# BuzzerBaseShieldv00.net
KiCad netlist of a schematic drawn in EAGLE
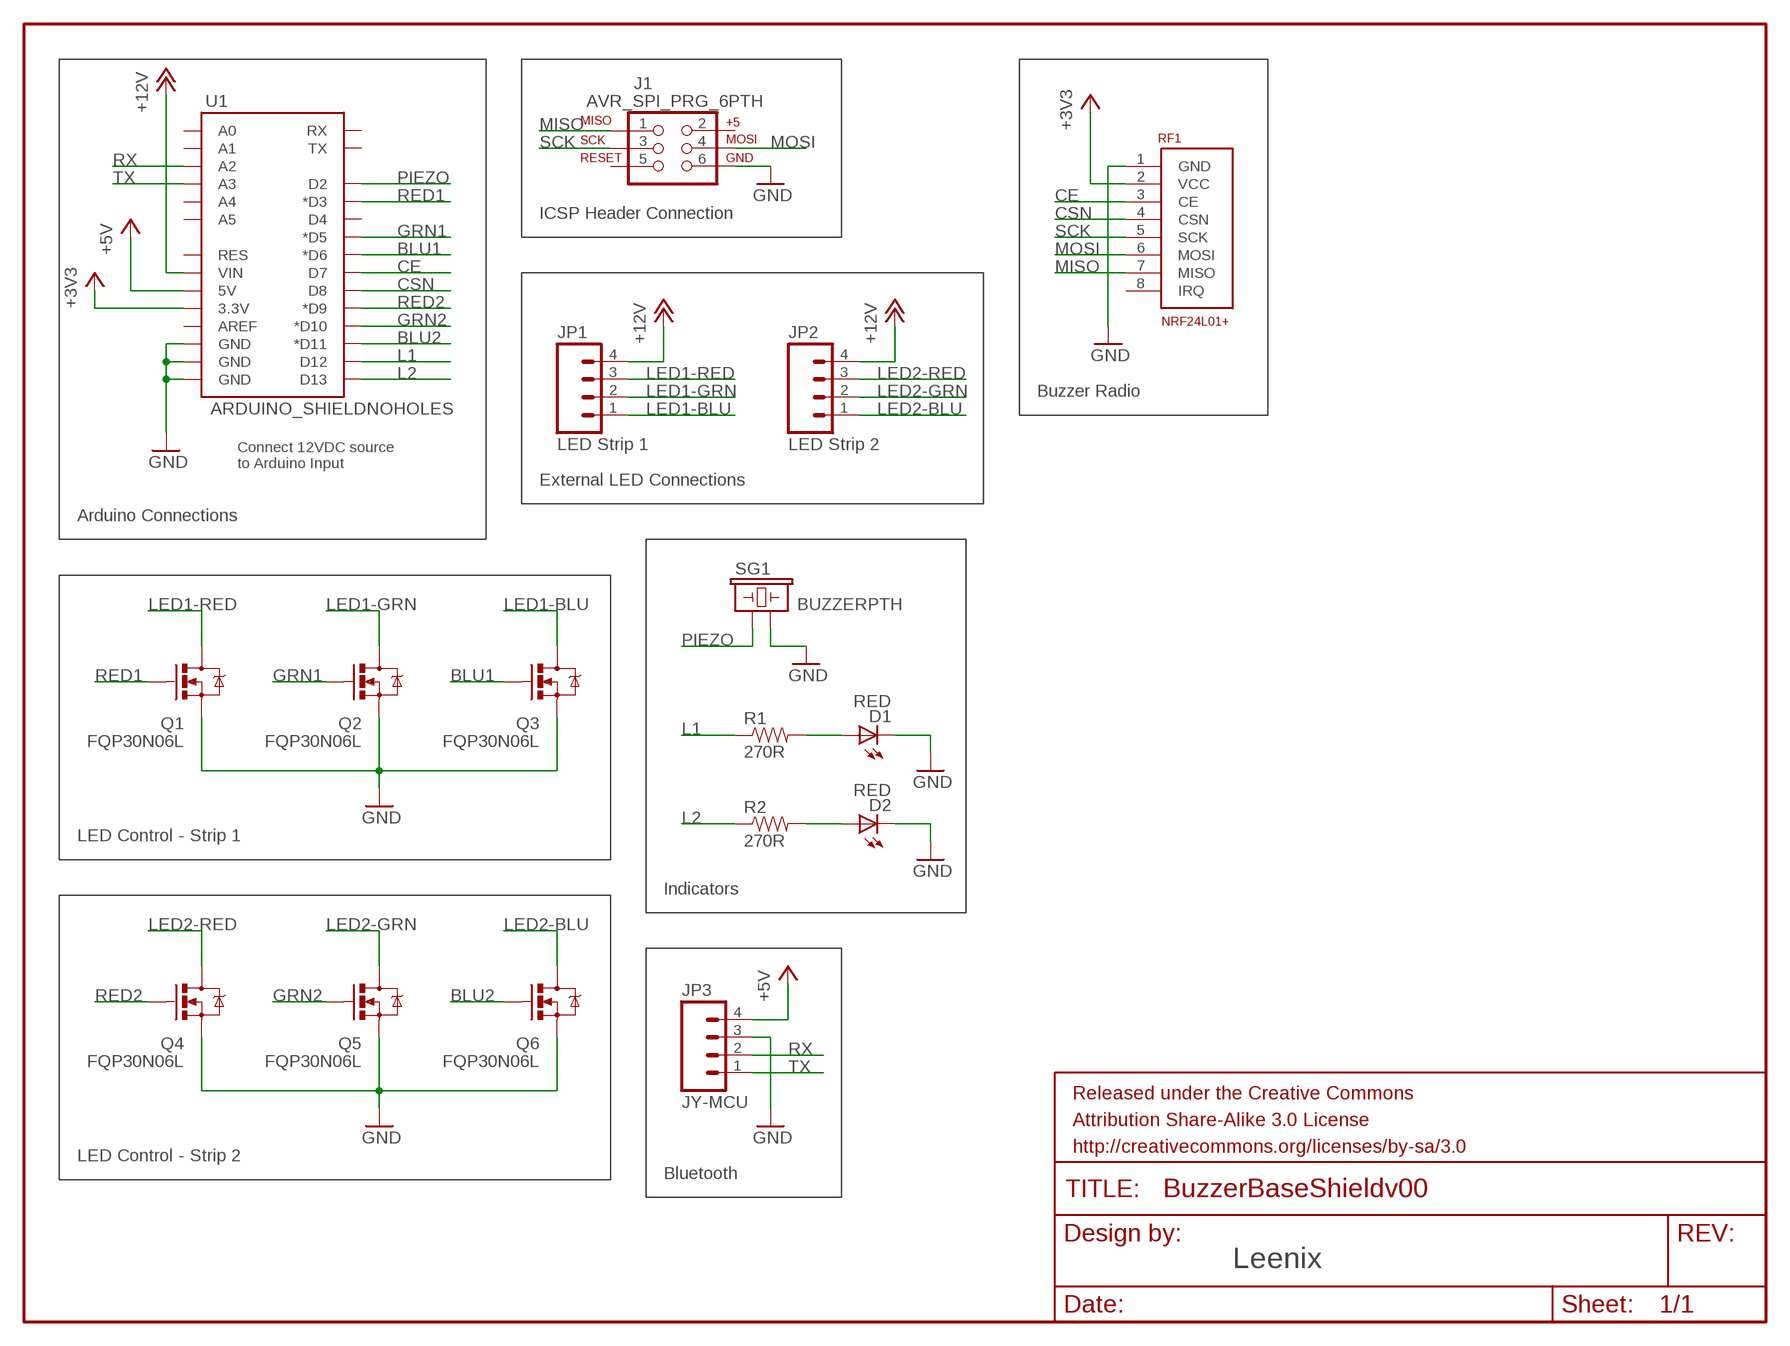
[diagram p0: schematic, sheet 1, part 1 of 2]
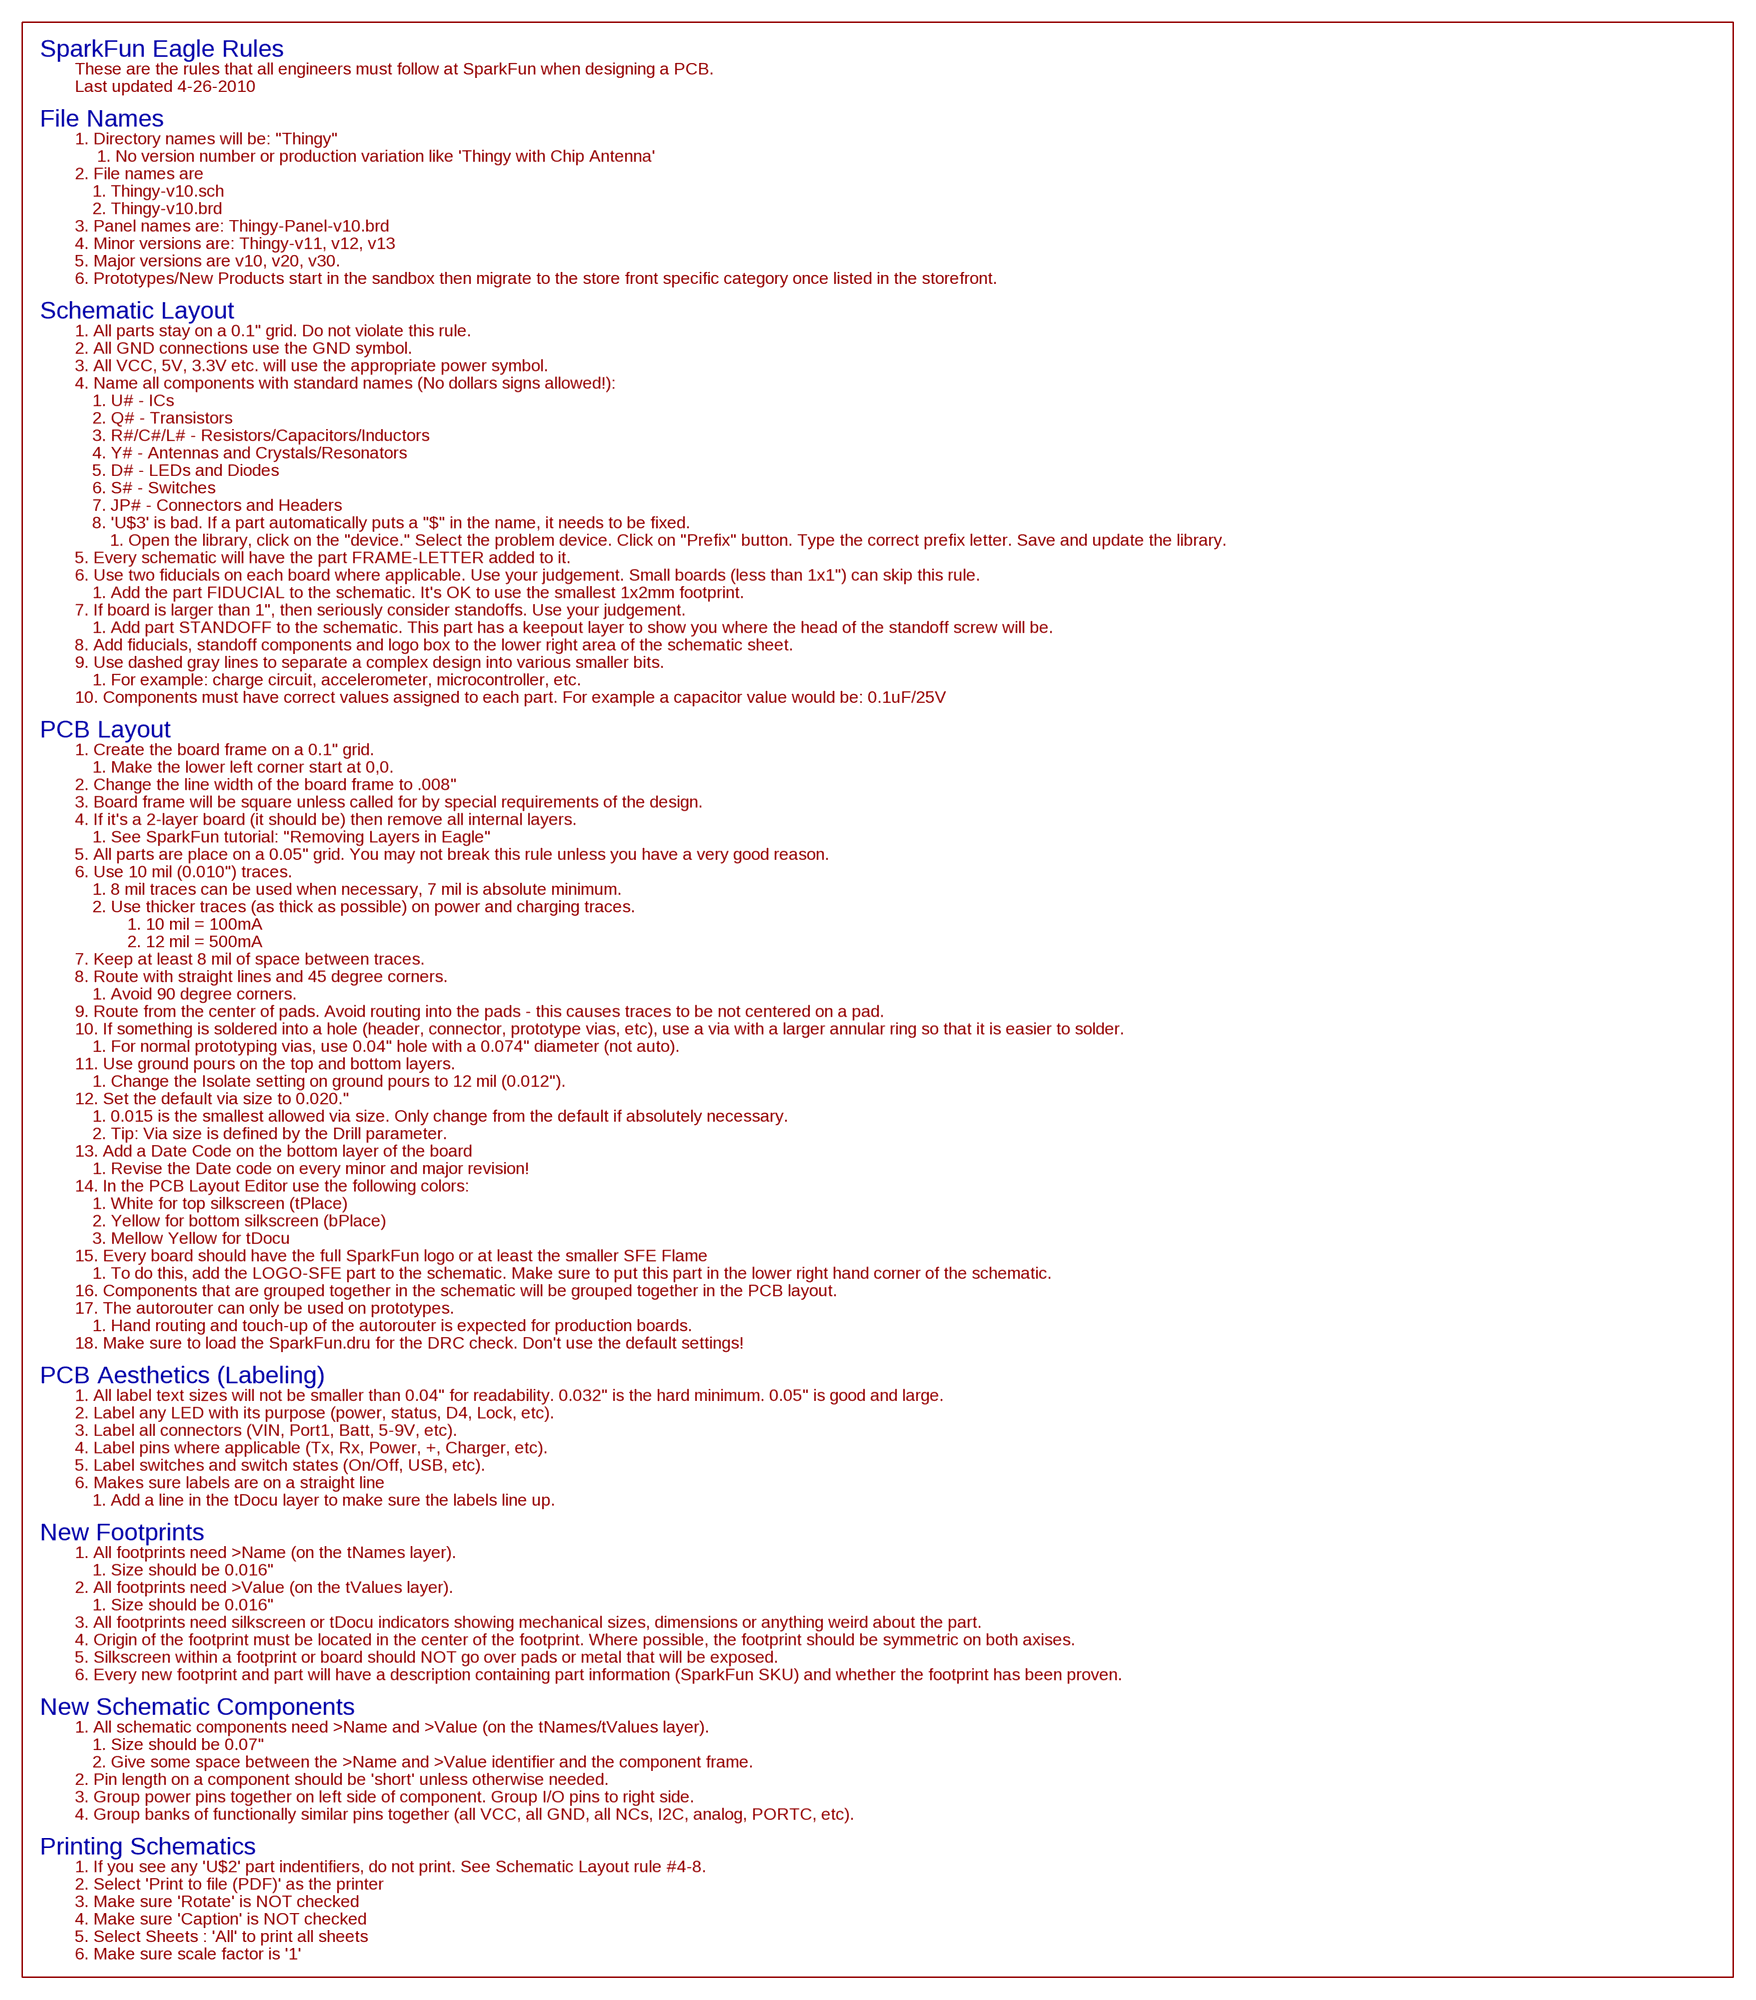
[diagram p1: schematic, sheet 1, part 2 of 2]

(export (version "E")
  (design (tool "Eeschema 10.0.6"))
  (components
    (comp (ref "D1")
      (value "RED")
      (footprint "eagle-import:LED-1206")
      (libsource (lib "eagle-import") (part "LED-RED1206"))
    )
    (comp (ref "D2")
      (value "RED")
      (footprint "eagle-import:LED-1206")
      (libsource (lib "eagle-import") (part "LED-RED1206"))
    )
    (comp (ref "FRAME1")
      (value "FRAME-LETTER")
      (footprint "eagle-import:CREATIVE_COMMONS")
      (libsource (lib "eagle-import") (part "FRAME-LETTER"))
    )
    (comp (ref "J1")
      (value "AVR_SPI_PRG_6PTH")
      (footprint "eagle-import:2X3")
      (libsource (lib "eagle-import") (part "AVR_SPI_PRG_6PTH"))
    )
    (comp (ref "JP1")
      (value "LED Strip 1")
      (footprint "eagle-import:1X04_LONGPADS")
      (libsource (lib "eagle-import") (part "M04LONGPADS"))
    )
    (comp (ref "JP2")
      (value "LED Strip 2")
      (footprint "eagle-import:1X04_LONGPADS")
      (libsource (lib "eagle-import") (part "M04LONGPADS"))
    )
    (comp (ref "JP3")
      (value "JY-MCU")
      (footprint "eagle-import:1X04")
      (libsource (lib "eagle-import") (part "M04PTH"))
    )
    (comp (ref "Q1")
      (value "FQP30N06L")
      (footprint "eagle-import:TO220V")
      (libsource (lib "eagle-import") (part "MOSFET-NCHANNELFQP30N06L"))
    )
    (comp (ref "Q2")
      (value "FQP30N06L")
      (footprint "eagle-import:TO220V")
      (libsource (lib "eagle-import") (part "MOSFET-NCHANNELFQP30N06L"))
    )
    (comp (ref "Q3")
      (value "FQP30N06L")
      (footprint "eagle-import:TO220V")
      (libsource (lib "eagle-import") (part "MOSFET-NCHANNELFQP30N06L"))
    )
    (comp (ref "Q4")
      (value "FQP30N06L")
      (footprint "eagle-import:TO220V")
      (libsource (lib "eagle-import") (part "MOSFET-NCHANNELFQP30N06L"))
    )
    (comp (ref "Q5")
      (value "FQP30N06L")
      (footprint "eagle-import:TO220V")
      (libsource (lib "eagle-import") (part "MOSFET-NCHANNELFQP30N06L"))
    )
    (comp (ref "Q6")
      (value "FQP30N06L")
      (footprint "eagle-import:TO220V")
      (libsource (lib "eagle-import") (part "MOSFET-NCHANNELFQP30N06L"))
    )
    (comp (ref "R1")
      (value "270R")
      (footprint "eagle-import:1206")
      (libsource (lib "eagle-import") (part "RESISTOR1206"))
    )
    (comp (ref "R2")
      (value "270R")
      (footprint "eagle-import:1206")
      (libsource (lib "eagle-import") (part "RESISTOR1206"))
    )
    (comp (ref "RF1")
      (value "NRF24L01+")
      (footprint "eagle-import:NRF24L01+-HEADER")
      (libsource (lib "eagle-import") (part "NRF24L01+"))
    )
    (comp (ref "SG1")
      (value "BUZZERPTH")
      (footprint "eagle-import:BUZZER-12MM")
      (libsource (lib "eagle-import") (part "BUZZERPTH"))
    )
    (comp (ref "U1")
      (value "ARDUINO_SHIELDNOHOLES")
      (footprint "eagle-import:DUEMILANOVE_SHIELD_NOHOLES")
      (libsource (lib "eagle-import") (part "ARDUINO_SHIELDNOHOLES"))
    )
  )
  (nets
    (net (code "1") (name "+3V3") (class "Default")
      (node (ref "RF1") (pin "2") (pinfunction "VCC_2") (pintype "power_in"))
      (node (ref "U1") (pin "3.3V") (pinfunction "3.3V_3.3V") (pintype "bidirectional"))
    )
    (net (code "2") (name "+5V") (class "Default")
      (node (ref "JP3") (pin "4") (pinfunction "4_4") (pintype "passive"))
      (node (ref "U1") (pin "5V") (pinfunction "5V_5V") (pintype "bidirectional"))
    )
    (net (code "3") (name "+12V") (class "Default")
      (node (ref "JP1") (pin "4") (pinfunction "4_4") (pintype "passive"))
      (node (ref "JP2") (pin "4") (pinfunction "4_4") (pintype "passive"))
      (node (ref "U1") (pin "VIN") (pinfunction "VIN_VIN") (pintype "bidirectional"))
    )
    (net (code "4") (name "/BLU1") (class "Default")
      (node (ref "Q3") (pin "1") (pinfunction "G_1") (pintype "passive"))
      (node (ref "U1") (pin "D6") (pinfunction "*D6_D6") (pintype "bidirectional"))
    )
    (net (code "5") (name "/BLU2") (class "Default")
      (node (ref "Q6") (pin "1") (pinfunction "G_1") (pintype "passive"))
      (node (ref "U1") (pin "D11") (pinfunction "*D11_D11") (pintype "bidirectional"))
    )
    (net (code "6") (name "/CE") (class "Default")
      (node (ref "RF1") (pin "3") (pinfunction "CE_3") (pintype "bidirectional"))
      (node (ref "U1") (pin "D7") (pinfunction "D7_D7") (pintype "bidirectional"))
    )
    (net (code "7") (name "/CSN") (class "Default")
      (node (ref "RF1") (pin "4") (pinfunction "CSN_4") (pintype "bidirectional"))
      (node (ref "U1") (pin "D8") (pinfunction "D8_D8") (pintype "bidirectional"))
    )
    (net (code "8") (name "/GRN1") (class "Default")
      (node (ref "Q2") (pin "1") (pinfunction "G_1") (pintype "passive"))
      (node (ref "U1") (pin "D5") (pinfunction "*D5_D5") (pintype "bidirectional"))
    )
    (net (code "9") (name "/GRN2") (class "Default")
      (node (ref "Q5") (pin "1") (pinfunction "G_1") (pintype "passive"))
      (node (ref "U1") (pin "D10") (pinfunction "*D10_D10") (pintype "bidirectional"))
    )
    (net (code "10") (name "/L1") (class "Default")
      (node (ref "R1") (pin "1") (pinfunction "1_1") (pintype "passive"))
      (node (ref "U1") (pin "D12") (pinfunction "D12_D12") (pintype "bidirectional"))
    )
    (net (code "11") (name "/L2") (class "Default")
      (node (ref "R2") (pin "1") (pinfunction "1_1") (pintype "passive"))
      (node (ref "U1") (pin "D13") (pinfunction "D13_D13") (pintype "bidirectional"))
    )
    (net (code "12") (name "/LED1-BLU") (class "Default")
      (node (ref "JP1") (pin "1") (pinfunction "1_1") (pintype "passive"))
      (node (ref "Q3") (pin "2") (pinfunction "D_2") (pintype "passive"))
    )
    (net (code "13") (name "/LED1-GRN") (class "Default")
      (node (ref "JP1") (pin "2") (pinfunction "2_2") (pintype "passive"))
      (node (ref "Q2") (pin "2") (pinfunction "D_2") (pintype "passive"))
    )
    (net (code "14") (name "/LED1-RED") (class "Default")
      (node (ref "JP1") (pin "3") (pinfunction "3_3") (pintype "passive"))
      (node (ref "Q1") (pin "2") (pinfunction "D_2") (pintype "passive"))
    )
    (net (code "15") (name "/LED2-BLU") (class "Default")
      (node (ref "JP2") (pin "1") (pinfunction "1_1") (pintype "passive"))
      (node (ref "Q6") (pin "2") (pinfunction "D_2") (pintype "passive"))
    )
    (net (code "16") (name "/LED2-GRN") (class "Default")
      (node (ref "JP2") (pin "2") (pinfunction "2_2") (pintype "passive"))
      (node (ref "Q5") (pin "2") (pinfunction "D_2") (pintype "passive"))
    )
    (net (code "17") (name "/LED2-RED") (class "Default")
      (node (ref "JP2") (pin "3") (pinfunction "3_3") (pintype "passive"))
      (node (ref "Q4") (pin "2") (pinfunction "D_2") (pintype "passive"))
    )
    (net (code "18") (name "/MISO") (class "Default")
      (node (ref "J1") (pin "1") (pinfunction "1_1") (pintype "passive"))
      (node (ref "RF1") (pin "7") (pinfunction "MISO_7") (pintype "bidirectional"))
    )
    (net (code "19") (name "/MOSI") (class "Default")
      (node (ref "J1") (pin "4") (pinfunction "4_4") (pintype "passive"))
      (node (ref "RF1") (pin "6") (pinfunction "MOSI_6") (pintype "bidirectional"))
    )
    (net (code "20") (name "/PIEZO") (class "Default")
      (node (ref "SG1") (pin "+") (pinfunction "1_+") (pintype "passive"))
      (node (ref "U1") (pin "D2") (pinfunction "D2_D2") (pintype "bidirectional"))
    )
    (net (code "21") (name "/RED1") (class "Default")
      (node (ref "Q1") (pin "1") (pinfunction "G_1") (pintype "passive"))
      (node (ref "U1") (pin "D3") (pinfunction "*D3_D3") (pintype "bidirectional"))
    )
    (net (code "22") (name "/RED2") (class "Default")
      (node (ref "Q4") (pin "1") (pinfunction "G_1") (pintype "passive"))
      (node (ref "U1") (pin "D9") (pinfunction "*D9_D9") (pintype "bidirectional"))
    )
    (net (code "23") (name "/RX") (class "Default")
      (node (ref "JP3") (pin "2") (pinfunction "2_2") (pintype "passive"))
      (node (ref "U1") (pin "A2") (pinfunction "A2_A2") (pintype "bidirectional"))
    )
    (net (code "24") (name "/SCK") (class "Default")
      (node (ref "J1") (pin "3") (pinfunction "3_3") (pintype "passive"))
      (node (ref "RF1") (pin "5") (pinfunction "SCK_5") (pintype "bidirectional"))
    )
    (net (code "25") (name "/TX") (class "Default")
      (node (ref "JP3") (pin "1") (pinfunction "1_1") (pintype "passive"))
      (node (ref "U1") (pin "A3") (pinfunction "A3_A3") (pintype "bidirectional"))
    )
    (net (code "26") (name "GND") (class "Default")
      (node (ref "D1") (pin "C") (pinfunction "C_C") (pintype "passive"))
      (node (ref "D2") (pin "C") (pinfunction "C_C") (pintype "passive"))
      (node (ref "J1") (pin "6") (pinfunction "6_6") (pintype "passive"))
      (node (ref "JP3") (pin "3") (pinfunction "3_3") (pintype "passive"))
      (node (ref "Q1") (pin "3") (pinfunction "S_3") (pintype "passive"))
      (node (ref "Q2") (pin "3") (pinfunction "S_3") (pintype "passive"))
      (node (ref "Q3") (pin "3") (pinfunction "S_3") (pintype "passive"))
      (node (ref "Q4") (pin "3") (pinfunction "S_3") (pintype "passive"))
      (node (ref "Q5") (pin "3") (pinfunction "S_3") (pintype "passive"))
      (node (ref "Q6") (pin "3") (pinfunction "S_3") (pintype "passive"))
      (node (ref "RF1") (pin "1") (pinfunction "GND_1") (pintype "power_in"))
      (node (ref "SG1") (pin "-") (pinfunction "2_-") (pintype "passive"))
      (node (ref "U1") (pin "GND@0") (pinfunction "GND_GND@0") (pintype "bidirectional"))
      (node (ref "U1") (pin "GND@1") (pinfunction "GND_GND@1") (pintype "bidirectional"))
      (node (ref "U1") (pin "GND@2") (pinfunction "GND_GND@2") (pintype "bidirectional"))
    )
    (net (code "27") (name "Net-(D1-PadA)") (class "Default")
      (node (ref "D1") (pin "A") (pinfunction "A_A") (pintype "passive"))
      (node (ref "R1") (pin "2") (pinfunction "2_2") (pintype "passive"))
    )
    (net (code "28") (name "Net-(D2-PadA)") (class "Default")
      (node (ref "D2") (pin "A") (pinfunction "A_A") (pintype "passive"))
      (node (ref "R2") (pin "2") (pinfunction "2_2") (pintype "passive"))
    )
    (net (code "29") (name "unconnected-(J1-Pad2)") (class "Default")
      (node (ref "J1") (pin "2") (pinfunction "2_2") (pintype "passive"))
    )
    (net (code "30") (name "unconnected-(J1-Pad5)") (class "Default")
      (node (ref "J1") (pin "5") (pinfunction "5_5") (pintype "passive"))
    )
    (net (code "31") (name "unconnected-(RF1-IRQ-Pad8)") (class "Default")
      (node (ref "RF1") (pin "8") (pinfunction "IRQ_8") (pintype "bidirectional"))
    )
    (net (code "32") (name "unconnected-(U1-PadA0)") (class "Default")
      (node (ref "U1") (pin "A0") (pinfunction "A0_A0") (pintype "bidirectional"))
    )
    (net (code "33") (name "unconnected-(U1-PadA1)") (class "Default")
      (node (ref "U1") (pin "A1") (pinfunction "A1_A1") (pintype "bidirectional"))
    )
    (net (code "34") (name "unconnected-(U1-PadA4)") (class "Default")
      (node (ref "U1") (pin "A4") (pinfunction "A4_A4") (pintype "bidirectional"))
    )
    (net (code "35") (name "unconnected-(U1-PadA5)") (class "Default")
      (node (ref "U1") (pin "A5") (pinfunction "A5_A5") (pintype "bidirectional"))
    )
    (net (code "36") (name "unconnected-(U1-PadAREF)") (class "Default")
      (node (ref "U1") (pin "AREF") (pinfunction "AREF_AREF") (pintype "bidirectional"))
    )
    (net (code "37") (name "unconnected-(U1-PadD4)") (class "Default")
      (node (ref "U1") (pin "D4") (pinfunction "D4_D4") (pintype "bidirectional"))
    )
    (net (code "38") (name "unconnected-(U1-PadRES)") (class "Default")
      (node (ref "U1") (pin "RES") (pinfunction "RES_RES") (pintype "bidirectional"))
    )
    (net (code "39") (name "unconnected-(U1-PadRX)") (class "Default")
      (node (ref "U1") (pin "RX") (pinfunction "RX_RX") (pintype "bidirectional"))
    )
    (net (code "40") (name "unconnected-(U1-PadTX)") (class "Default")
      (node (ref "U1") (pin "TX") (pinfunction "TX_TX") (pintype "bidirectional"))
    )
  )
)
